# power.net
KiCad netlist of a schematic drawn in Altium Designer
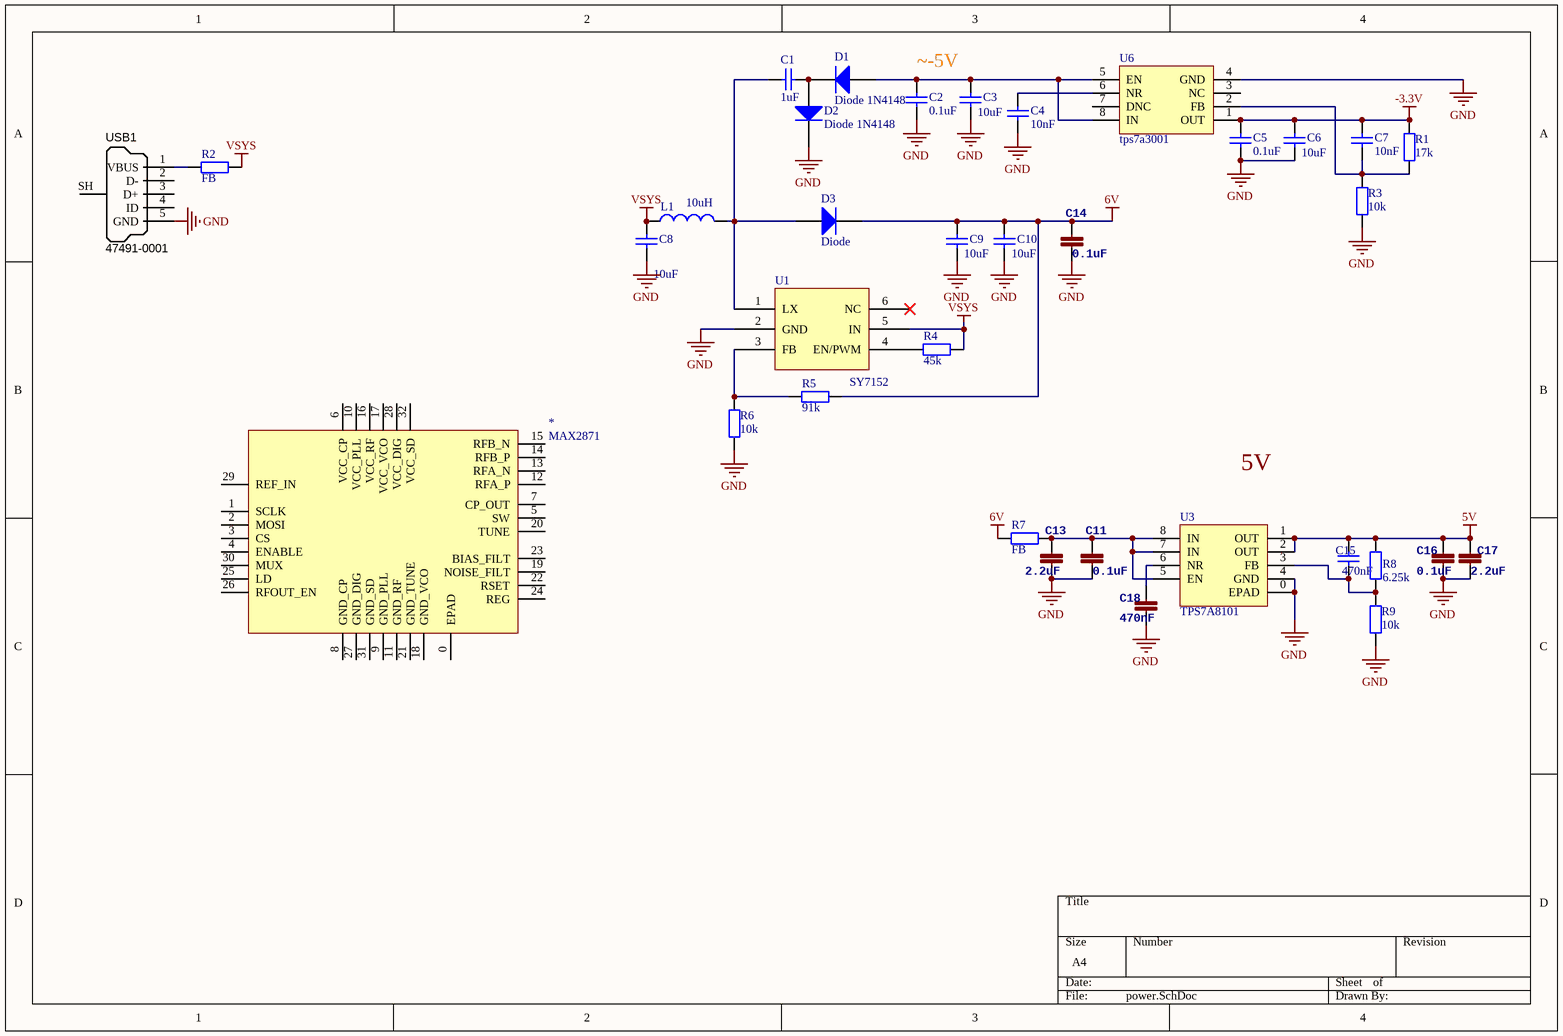
[diagram p0: power.SchDoc]

(export (version "E")
  (design (tool "Eeschema 10.0.6"))
  (components
    (comp (ref "*") (value "MAX2871") (footprint "MAX2871") (libsource (lib "F4SDR") (part "MAX2871")))
    (comp (ref "C1")
      (value "1uF")
      (footprint "0603")
      (description "Capacitor")
      (fields (field (name "PUBLISHER") "Altium Limited"))
      (libsource (lib "RTC6705") (part "Cap"))
    )
    (comp (ref "C2")
      (value "0.1uF")
      (footprint "0603")
      (description "Capacitor")
      (fields (field (name "PUBLISHER") "Altium Limited"))
      (libsource (lib "RTC6705") (part "Cap"))
    )
    (comp (ref "C3")
      (value "10uF")
      (footprint "0805")
      (description "Capacitor")
      (fields (field (name "PUBLISHER") "Altium Limited"))
      (libsource (lib "RTC6705") (part "Cap"))
    )
    (comp (ref "C4")
      (value "10nF")
      (footprint "0402")
      (description "Capacitor")
      (fields (field (name "PUBLISHER") "Altium Limited"))
      (libsource (lib "RTC6705") (part "Cap"))
    )
    (comp (ref "C5")
      (value "0.1uF")
      (footprint "0603")
      (description "Capacitor")
      (fields (field (name "PUBLISHER") "Altium Limited"))
      (libsource (lib "RTC6705") (part "Cap"))
    )
    (comp (ref "C6")
      (value "10uF")
      (footprint "0805")
      (description "Capacitor")
      (fields (field (name "PUBLISHER") "Altium Limited"))
      (libsource (lib "RTC6705") (part "Cap"))
    )
    (comp (ref "C7")
      (value "10nF")
      (footprint "0402")
      (description "Capacitor")
      (fields (field (name "PUBLISHER") "Altium Limited"))
      (libsource (lib "RTC6705") (part "Cap"))
    )
    (comp (ref "C8")
      (value "10uF")
      (footprint "0805")
      (description "Capacitor")
      (fields (field (name "PUBLISHER") "Altium Limited"))
      (libsource (lib "RTC6705") (part "Cap"))
    )
    (comp (ref "C9")
      (value "10uF")
      (footprint "0805")
      (description "Capacitor")
      (fields (field (name "PUBLISHER") "Altium Limited"))
      (libsource (lib "RTC6705") (part "Cap"))
    )
    (comp (ref "C10")
      (value "10uF")
      (footprint "0805")
      (description "Capacitor")
      (fields (field (name "PUBLISHER") "Altium Limited"))
      (libsource (lib "RTC6705") (part "Cap"))
    )
    (comp (ref "C11")
      (value "0.1uF")
      (footprint "0402")
      (description "<b>Capacitor</b>\nStandard 0603 ceramic capacitor, and 0.1\" leaded capacitor.")
      (fields (field (name "PARTNO") "CC0402ZRY5V7BB104"))
      (libsource (lib "*") (part "CAP0402-CAP"))
    )
    (comp (ref "C13")
      (value "2.2uF")
      (footprint "0603")
      (description "<b>Capacitor</b>\nStandard 0603 ceramic capacitor, and 0.1\" leaded capacitor.")
      (fields (field (name "PARTNO") "CC0402ZRY5V7BB104"))
      (libsource (lib "pixhawk2") (part "CAP0402-CAP"))
    )
    (comp (ref "C14")
      (value "0.1uF")
      (footprint "0402")
      (description "<b>Capacitor</b>\nStandard 0603 ceramic capacitor, and 0.1\" leaded capacitor.")
      (fields (field (name "PARTNO") "CC0402ZRY5V7BB104"))
      (libsource (lib "*") (part "CAP0402-CAP"))
    )
    (comp (ref "C15")
      (value "470nF")
      (footprint "0402")
      (description "Capacitor")
      (fields (field (name "PUBLISHER") "Altium Limited"))
      (libsource (lib "RTC6705") (part "Cap"))
    )
    (comp (ref "C16")
      (value "0.1uF")
      (footprint "0603")
      (description "<b>Capacitor</b>\nStandard 0603 ceramic capacitor, and 0.1\" leaded capacitor.")
      (fields (field (name "PARTNO") "CC0402ZRY5V7BB104"))
      (libsource (lib "*") (part "CAP0402-CAP"))
    )
    (comp (ref "C17")
      (value "2.2uF")
      (footprint "0603")
      (description "<b>Capacitor</b>\nStandard 0603 ceramic capacitor, and 0.1\" leaded capacitor.")
      (fields (field (name "PARTNO") "CC0402ZRY5V7BB104"))
      (libsource (lib "pixhawk2") (part "CAP0402-CAP"))
    )
    (comp (ref "C18")
      (value "470nF")
      (footprint "0402")
      (description "<b>Capacitor</b>\nStandard 0603 ceramic capacitor, and 0.1\" leaded capacitor.")
      (fields (field (name "PARTNO") "CC0402ZRY5V7BB104"))
      (libsource (lib "*") (part "CAP0402-CAP"))
    )
    (comp (ref "D1")
      (value "Diode 1N4148")
      (footprint "LC-SOD-323")
      (description "High Conductance Fast Diode")
      (fields (field (name "PUBLISHER") "Altium Limited"))
      (libsource (lib "Miscellaneous Devices") (part "Diode 1N4148"))
    )
    (comp (ref "D2")
      (value "Diode 1N4148")
      (footprint "LC-SOD-323")
      (description "High Conductance Fast Diode")
      (fields (field (name "PUBLISHER") "Altium Limited"))
      (libsource (lib "Miscellaneous Devices") (part "Diode 1N4148"))
    )
    (comp (ref "D3")
      (value "Diode")
      (footprint "LC-SOD-323")
      (description "Default Diode")
      (fields (field (name "PUBLISHER") "Altium Limited"))
      (libsource (lib "Miscellaneous Devices") (part "Diode"))
    )
    (comp (ref "L1")
      (value "10uH")
      (footprint "L4015")
      (description "Inductor")
      (fields (field (name "PUBLISHER") "Altium Limited"))
      (libsource (lib "Miscellaneous Devices") (part "Inductor"))
    )
    (comp (ref "R1")
      (value "17k")
      (footprint "0402")
      (description "Resistor")
      (fields (field (name "PUBLISHER") "Altium Limited"))
      (libsource (lib "") (part "Res2_1"))
    )
    (comp (ref "R2")
      (value "FB")
      (footprint "0603")
      (description "Resistor")
      (fields (field (name "PUBLISHER") "Altium Limited"))
      (libsource (lib "RTC6705") (part "Res2"))
    )
    (comp (ref "R3")
      (value "10k")
      (footprint "0402")
      (description "Resistor")
      (fields (field (name "PUBLISHER") "Altium Limited"))
      (libsource (lib "") (part "Res2_1"))
    )
    (comp (ref "R4")
      (value "45k")
      (footprint "0402")
      (description "Resistor")
      (fields (field (name "PUBLISHER") "Altium Limited"))
      (libsource (lib "RTC6705") (part "Res2"))
    )
    (comp (ref "R5")
      (value "91k")
      (footprint "0402")
      (description "Resistor")
      (fields (field (name "PUBLISHER") "Altium Limited"))
      (libsource (lib "RTC6705") (part "Res2"))
    )
    (comp (ref "R6")
      (value "10k")
      (footprint "0402")
      (description "Resistor")
      (fields (field (name "PUBLISHER") "Altium Limited"))
      (libsource (lib "") (part "Res2_1"))
    )
    (comp (ref "R7")
      (value "FB")
      (footprint "0603")
      (description "Resistor")
      (fields (field (name "PUBLISHER") "Altium Limited"))
      (libsource (lib "Miscellaneous Devices") (part "Res2"))
    )
    (comp (ref "R8")
      (value "6.25k")
      (footprint "0402")
      (description "Resistor")
      (fields (field (name "PUBLISHER") "Altium Limited"))
      (libsource (lib "") (part "Res2_1"))
    )
    (comp (ref "R9")
      (value "10k")
      (footprint "0402")
      (description "Resistor")
      (fields (field (name "PUBLISHER") "Altium Limited"))
      (libsource (lib "") (part "Res2_1"))
    )
    (comp (ref "U1") (value "SY7152") (footprint "SOT23-6") (libsource (lib "sch") (part "SY7152")))
    (comp (ref "U3") (value "TPS7A8101") (footprint "TPS7A8101") (libsource (lib "F4SDR") (part "TPS7A8101")))
    (comp (ref "U6")
      (value "tps7a3001")
      (footprint "MSOP8/VSSOP8")
      (libsource (lib "F4SDR") (part "tps7a3001"))
    )
    (comp (ref "USB1")
      (value "USB Micro Type B")
      (footprint "MICRO-YZX")
      (description "Connector SMD USB Micro Type B middle mount")
      (fields (field (name "MANUFACTURER PART NUMBER 1") "47491-0001"))
      (libsource (lib "PBL - Connectors") (part "USB_Micro_TypeB"))
    )
  )
  (nets
    (net (code "1") (name "-3.3V") (class "Default")
      (node (ref "C5") (pin "1") (pinfunction "1_1") (pintype "passive"))
      (node (ref "C6") (pin "2") (pinfunction "2_2") (pintype "passive"))
      (node (ref "C7") (pin "1") (pinfunction "1_1") (pintype "passive"))
      (node (ref "R1") (pin "2") (pinfunction "2_2") (pintype "passive"))
      (node (ref "U6") (pin "1") (pinfunction "OUT_1") (pintype "passive"))
    )
    (net (code "2") (name "5V") (class "Default")
      (node (ref "C15") (pin "1") (pinfunction "1_1") (pintype "passive"))
      (node (ref "C16") (pin "2") (pinfunction "2_2") (pintype "passive"))
      (node (ref "C17") (pin "2") (pinfunction "2_2") (pintype "passive"))
      (node (ref "R8") (pin "1") (pinfunction "1_1") (pintype "passive"))
      (node (ref "U3") (pin "1") (pinfunction "OUT_1") (pintype "passive"))
      (node (ref "U3") (pin "2") (pinfunction "OUT_2") (pintype "passive"))
    )
    (net (code "3") (name "6V") (class "Default")
      (node (ref "C10") (pin "2") (pinfunction "2_2") (pintype "passive"))
      (node (ref "C14") (pin "2") (pinfunction "2_2") (pintype "passive"))
      (node (ref "C9") (pin "2") (pinfunction "2_2") (pintype "passive"))
      (node (ref "D3") (pin "2") (pinfunction "K_2") (pintype "passive"))
      (node (ref "R5") (pin "2") (pinfunction "2_2") (pintype "passive"))
      (node (ref "R7") (pin "2") (pinfunction "2_2") (pintype "passive"))
    )
    (net (code "4") (name "GND") (class "Default")
      (node (ref "C10") (pin "1") (pinfunction "1_1") (pintype "passive"))
      (node (ref "C11") (pin "1") (pinfunction "1_1") (pintype "passive"))
      (node (ref "C13") (pin "1") (pinfunction "1_1") (pintype "passive"))
      (node (ref "C14") (pin "1") (pinfunction "1_1") (pintype "passive"))
      (node (ref "C16") (pin "1") (pinfunction "1_1") (pintype "passive"))
      (node (ref "C17") (pin "1") (pinfunction "1_1") (pintype "passive"))
      (node (ref "C18") (pin "1") (pinfunction "1_1") (pintype "passive"))
      (node (ref "C2") (pin "2") (pinfunction "2_2") (pintype "passive"))
      (node (ref "C3") (pin "1") (pinfunction "1_1") (pintype "passive"))
      (node (ref "C4") (pin "2") (pinfunction "2_2") (pintype "passive"))
      (node (ref "C5") (pin "2") (pinfunction "2_2") (pintype "passive"))
      (node (ref "C6") (pin "1") (pinfunction "1_1") (pintype "passive"))
      (node (ref "C8") (pin "1") (pinfunction "1_1") (pintype "passive"))
      (node (ref "C9") (pin "1") (pinfunction "1_1") (pintype "passive"))
      (node (ref "D2") (pin "2") (pinfunction "K_2") (pintype "passive"))
      (node (ref "R3") (pin "1") (pinfunction "1_1") (pintype "passive"))
      (node (ref "R6") (pin "1") (pinfunction "1_1") (pintype "passive"))
      (node (ref "R9") (pin "2") (pinfunction "2_2") (pintype "passive"))
      (node (ref "U1") (pin "2") (pinfunction "GND_2") (pintype "passive"))
      (node (ref "U3") (pin "0") (pinfunction "EPAD_0") (pintype "passive"))
      (node (ref "U3") (pin "4") (pinfunction "GND_4") (pintype "passive"))
      (node (ref "U6") (pin "4") (pinfunction "GND_4") (pintype "passive"))
      (node (ref "USB1") (pin "5") (pinfunction "GND_5") (pintype "passive"))
    )
    (net (code "5") (name "Net-(D1-A)") (class "Default")
      (node (ref "C2") (pin "1") (pinfunction "1_1") (pintype "passive"))
      (node (ref "C3") (pin "2") (pinfunction "2_2") (pintype "passive"))
      (node (ref "D1") (pin "1") (pinfunction "A_1") (pintype "passive"))
      (node (ref "U6") (pin "5") (pinfunction "EN_5") (pintype "passive"))
      (node (ref "U6") (pin "8") (pinfunction "IN_8") (pintype "passive"))
    )
    (net (code "6") (name "Net-(D1-K)") (class "Default")
      (node (ref "C1") (pin "1") (pinfunction "1_1") (pintype "passive"))
      (node (ref "D1") (pin "2") (pinfunction "K_2") (pintype "passive"))
      (node (ref "D2") (pin "1") (pinfunction "A_1") (pintype "passive"))
    )
    (net (code "7") (name "Net-(D3-A)") (class "Default")
      (node (ref "C1") (pin "2") (pinfunction "2_2") (pintype "passive"))
      (node (ref "D3") (pin "1") (pinfunction "A_1") (pintype "passive"))
      (node (ref "L1") (pin "2") (pinfunction "2_2") (pintype "passive"))
      (node (ref "U1") (pin "1") (pinfunction "LX_1") (pintype "passive"))
    )
    (net (code "8") (name "Net-(U1-EN{slash}PWM)") (class "Default")
      (node (ref "R4") (pin "1") (pinfunction "1_1") (pintype "passive"))
      (node (ref "U1") (pin "4") (pinfunction "EN/PWM_4") (pintype "passive"))
    )
    (net (code "9") (name "Net-(U1-FB)") (class "Default")
      (node (ref "R5") (pin "1") (pinfunction "1_1") (pintype "passive"))
      (node (ref "R6") (pin "2") (pinfunction "2_2") (pintype "passive"))
      (node (ref "U1") (pin "3") (pinfunction "FB_3") (pintype "passive"))
    )
    (net (code "10") (name "Net-(U3-EN)") (class "Default")
      (node (ref "C11") (pin "2") (pinfunction "2_2") (pintype "passive"))
      (node (ref "C13") (pin "2") (pinfunction "2_2") (pintype "passive"))
      (node (ref "R7") (pin "1") (pinfunction "1_1") (pintype "passive"))
      (node (ref "U3") (pin "5") (pinfunction "EN_5") (pintype "passive"))
      (node (ref "U3") (pin "7") (pinfunction "IN_7") (pintype "passive"))
      (node (ref "U3") (pin "8") (pinfunction "IN_8") (pintype "passive"))
    )
    (net (code "11") (name "Net-(U3-FB)") (class "Default")
      (node (ref "C15") (pin "2") (pinfunction "2_2") (pintype "passive"))
      (node (ref "R8") (pin "2") (pinfunction "2_2") (pintype "passive"))
      (node (ref "R9") (pin "1") (pinfunction "1_1") (pintype "passive"))
      (node (ref "U3") (pin "3") (pinfunction "FB_3") (pintype "passive"))
    )
    (net (code "12") (name "Net-(U3-NR)") (class "Default")
      (node (ref "C18") (pin "2") (pinfunction "2_2") (pintype "passive"))
      (node (ref "U3") (pin "6") (pinfunction "NR_6") (pintype "passive"))
    )
    (net (code "13") (name "Net-(U6-FB)") (class "Default")
      (node (ref "C7") (pin "2") (pinfunction "2_2") (pintype "passive"))
      (node (ref "R1") (pin "1") (pinfunction "1_1") (pintype "passive"))
      (node (ref "R3") (pin "2") (pinfunction "2_2") (pintype "passive"))
      (node (ref "U6") (pin "2") (pinfunction "FB_2") (pintype "passive"))
    )
    (net (code "14") (name "Net-(U6-NR)") (class "Default")
      (node (ref "C4") (pin "1") (pinfunction "1_1") (pintype "passive"))
      (node (ref "U6") (pin "6") (pinfunction "NR_6") (pintype "passive"))
    )
    (net (code "15") (name "Net-(USB1-VBUS)") (class "Default")
      (node (ref "R2") (pin "1") (pinfunction "1_1") (pintype "passive"))
      (node (ref "USB1") (pin "1") (pinfunction "VBUS_1") (pintype "passive"))
    )
    (net (code "16") (name "VSYS") (class "Default")
      (node (ref "C8") (pin "2") (pinfunction "2_2") (pintype "passive"))
      (node (ref "L1") (pin "1") (pinfunction "1_1") (pintype "passive"))
      (node (ref "R2") (pin "2") (pinfunction "2_2") (pintype "passive"))
      (node (ref "R4") (pin "2") (pinfunction "2_2") (pintype "passive"))
      (node (ref "U1") (pin "5") (pinfunction "IN_5") (pintype "passive"))
    )
    (net (code "17") (name "unconnected-(*-BIAS_FILT-Pad23)") (class "Default")
      (node (ref "*") (pin "23") (pinfunction "BIAS_FILT_23") (pintype "passive"))
    )
    (net (code "18") (name "unconnected-(*-CP_OUT-Pad7)") (class "Default")
      (node (ref "*") (pin "7") (pinfunction "CP_OUT_7") (pintype "passive"))
    )
    (net (code "19") (name "unconnected-(*-CS-Pad3)") (class "Default")
      (node (ref "*") (pin "3") (pinfunction "CS_3") (pintype "passive"))
    )
    (net (code "20") (name "unconnected-(*-ENABLE-Pad4)") (class "Default")
      (node (ref "*") (pin "4") (pinfunction "ENABLE_4") (pintype "passive"))
    )
    (net (code "21") (name "unconnected-(*-EPAD-Pad0)") (class "Default")
      (node (ref "*") (pin "0") (pinfunction "EPAD_0") (pintype "passive"))
    )
    (net (code "22") (name "unconnected-(*-GND_CP-Pad8)") (class "Default")
      (node (ref "*") (pin "8") (pinfunction "GND_CP_8") (pintype "passive"))
    )
    (net (code "23") (name "unconnected-(*-GND_DIG-Pad27)") (class "Default")
      (node (ref "*") (pin "27") (pinfunction "GND_DIG_27") (pintype "passive"))
    )
    (net (code "24") (name "unconnected-(*-GND_PLL-Pad9)") (class "Default")
      (node (ref "*") (pin "9") (pinfunction "GND_PLL_9") (pintype "passive"))
    )
    (net (code "25") (name "unconnected-(*-GND_RF-Pad11)") (class "Default")
      (node (ref "*") (pin "11") (pinfunction "GND_RF_11") (pintype "passive"))
    )
    (net (code "26") (name "unconnected-(*-GND_SD-Pad31)") (class "Default")
      (node (ref "*") (pin "31") (pinfunction "GND_SD_31") (pintype "passive"))
    )
    (net (code "27") (name "unconnected-(*-GND_TUNE-Pad21)") (class "Default")
      (node (ref "*") (pin "21") (pinfunction "GND_TUNE_21") (pintype "passive"))
    )
    (net (code "28") (name "unconnected-(*-GND_VCO-Pad18)") (class "Default")
      (node (ref "*") (pin "18") (pinfunction "GND_VCO_18") (pintype "passive"))
    )
    (net (code "29") (name "unconnected-(*-LD-Pad25)") (class "Default")
      (node (ref "*") (pin "25") (pinfunction "LD_25") (pintype "passive"))
    )
    (net (code "30") (name "unconnected-(*-MOSI-Pad2)") (class "Default")
      (node (ref "*") (pin "2") (pinfunction "MOSI_2") (pintype "passive"))
    )
    (net (code "31") (name "unconnected-(*-MUX-Pad30)") (class "Default")
      (node (ref "*") (pin "30") (pinfunction "MUX_30") (pintype "passive"))
    )
    (net (code "32") (name "unconnected-(*-NOISE_FILT-Pad19)") (class "Default")
      (node (ref "*") (pin "19") (pinfunction "NOISE_FILT_19") (pintype "passive"))
    )
    (net (code "33") (name "unconnected-(*-REF_IN-Pad29)") (class "Default")
      (node (ref "*") (pin "29") (pinfunction "REF_IN_29") (pintype "passive"))
    )
    (net (code "34") (name "unconnected-(*-REG-Pad24)") (class "Default")
      (node (ref "*") (pin "24") (pinfunction "REG_24") (pintype "passive"))
    )
    (net (code "35") (name "unconnected-(*-RFA_N-Pad13)") (class "Default")
      (node (ref "*") (pin "13") (pinfunction "RFA_N_13") (pintype "passive"))
    )
    (net (code "36") (name "unconnected-(*-RFA_P-Pad12)") (class "Default")
      (node (ref "*") (pin "12") (pinfunction "RFA_P_12") (pintype "passive"))
    )
    (net (code "37") (name "unconnected-(*-RFB_N-Pad15)") (class "Default")
      (node (ref "*") (pin "15") (pinfunction "RFB_N_15") (pintype "passive"))
    )
    (net (code "38") (name "unconnected-(*-RFB_P-Pad14)") (class "Default")
      (node (ref "*") (pin "14") (pinfunction "RFB_P_14") (pintype "passive"))
    )
    (net (code "39") (name "unconnected-(*-RFOUT_EN-Pad26)") (class "Default")
      (node (ref "*") (pin "26") (pinfunction "RFOUT_EN_26") (pintype "passive"))
    )
    (net (code "40") (name "unconnected-(*-RSET-Pad22)") (class "Default")
      (node (ref "*") (pin "22") (pinfunction "RSET_22") (pintype "passive"))
    )
    (net (code "41") (name "unconnected-(*-SCLK-Pad1)") (class "Default")
      (node (ref "*") (pin "1") (pinfunction "SCLK_1") (pintype "passive"))
    )
    (net (code "42") (name "unconnected-(*-SW-Pad5)") (class "Default")
      (node (ref "*") (pin "5") (pinfunction "SW_5") (pintype "passive"))
    )
    (net (code "43") (name "unconnected-(*-TUNE-Pad20)") (class "Default")
      (node (ref "*") (pin "20") (pinfunction "TUNE_20") (pintype "passive"))
    )
    (net (code "44") (name "unconnected-(*-VCC_CP-Pad6)") (class "Default")
      (node (ref "*") (pin "6") (pinfunction "VCC_CP_6") (pintype "passive"))
    )
    (net (code "45") (name "unconnected-(*-VCC_DIG-Pad28)") (class "Default")
      (node (ref "*") (pin "28") (pinfunction "VCC_DIG_28") (pintype "passive"))
    )
    (net (code "46") (name "unconnected-(*-VCC_PLL-Pad10)") (class "Default")
      (node (ref "*") (pin "10") (pinfunction "VCC_PLL_10") (pintype "passive"))
    )
    (net (code "47") (name "unconnected-(*-VCC_RF-Pad16)") (class "Default")
      (node (ref "*") (pin "16") (pinfunction "VCC_RF_16") (pintype "passive"))
    )
    (net (code "48") (name "unconnected-(*-VCC_SD-Pad32)") (class "Default")
      (node (ref "*") (pin "32") (pinfunction "VCC_SD_32") (pintype "passive"))
    )
    (net (code "49") (name "unconnected-(*-VCC_VCO-Pad17)") (class "Default")
      (node (ref "*") (pin "17") (pinfunction "VCC_VCO_17") (pintype "passive"))
    )
    (net (code "50") (name "unconnected-(U1-NC-Pad6)") (class "Default")
      (node (ref "U1") (pin "6") (pinfunction "NC_6") (pintype "passive+no_connect"))
    )
    (net (code "51") (name "unconnected-(U6-DNC-Pad7)") (class "Default")
      (node (ref "U6") (pin "7") (pinfunction "DNC_7") (pintype "passive"))
    )
    (net (code "52") (name "unconnected-(U6-NC-Pad3)") (class "Default")
      (node (ref "U6") (pin "3") (pinfunction "NC_3") (pintype "passive"))
    )
    (net (code "53") (name "unconnected-(USB1-D+-Pad3)") (class "Default")
      (node (ref "USB1") (pin "3") (pinfunction "D+_3") (pintype "passive"))
    )
    (net (code "54") (name "unconnected-(USB1-D--Pad2)") (class "Default")
      (node (ref "USB1") (pin "2") (pinfunction "D-_2") (pintype "passive"))
    )
    (net (code "55") (name "unconnected-(USB1-ID-Pad4)") (class "Default")
      (node (ref "USB1") (pin "4") (pinfunction "ID_4") (pintype "passive"))
    )
    (net (code "56") (name "unconnected-(USB1-Shell-PadSH)") (class "Default")
      (node (ref "USB1") (pin "SH") (pinfunction "Shell_SH") (pintype "passive"))
    )
  )
)
